# ole_fatchain.net
KiCad netlist of a schematic drawn in Altium Designer
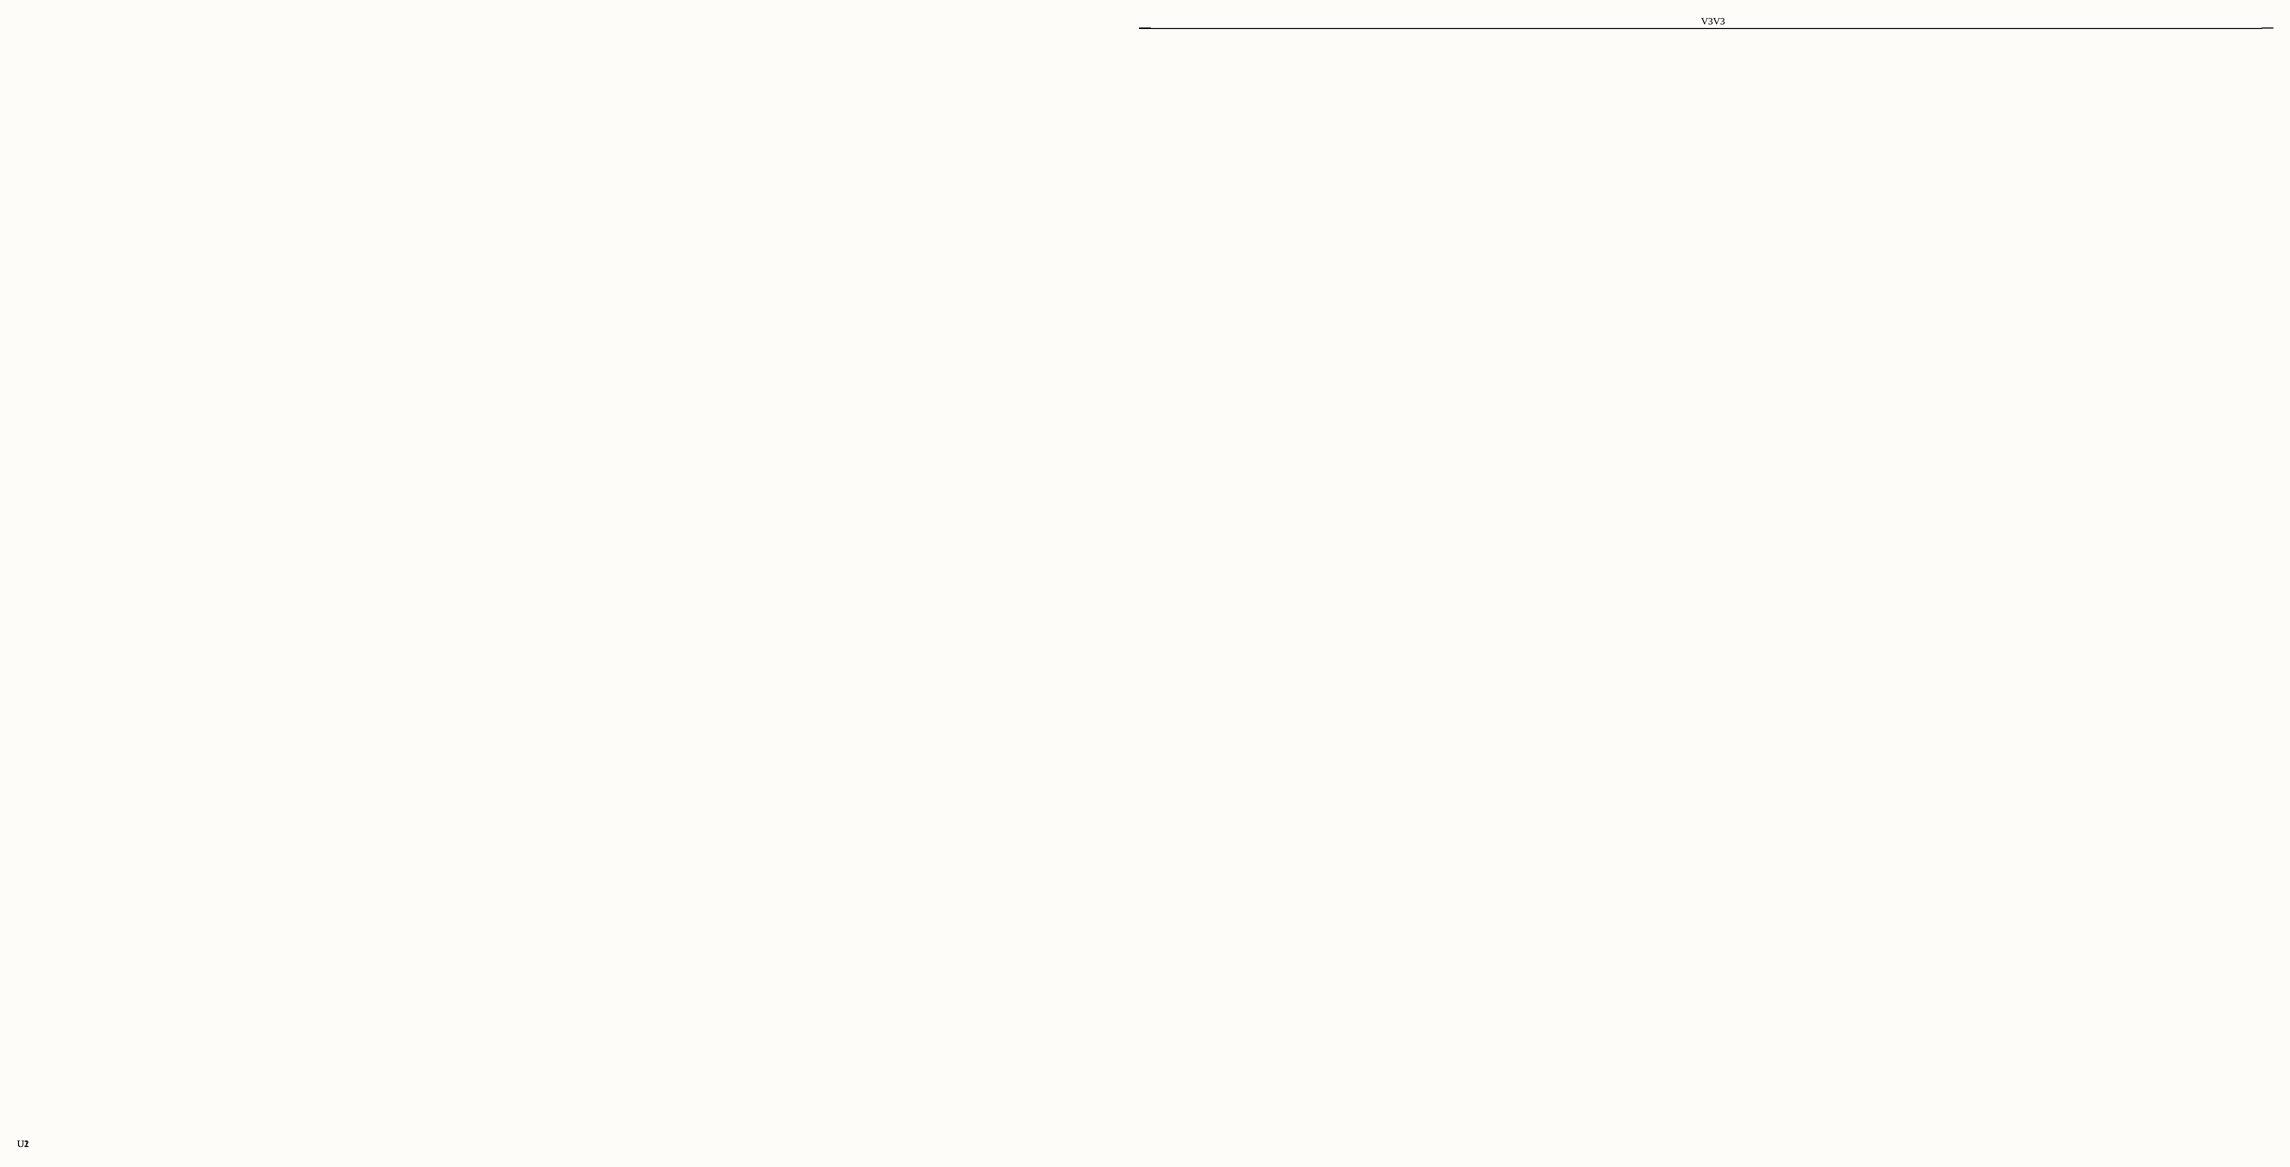
[diagram p0: ole_fatchain.SchDoc]

(export (version "E")
  (design (tool "Eeschema 10.0.6"))
  (components
    (comp (ref "U1") (value "~") (libsource (lib "altium-import") (part "root_0_RES_")))
    (comp (ref "U2") (value "~") (libsource (lib "altium-import") (part "root_0_CAP_")))
  )
  (nets
    (net (code "1") (name "/V3V3") (class "Default")
      (node (ref "U1") (pin "1") (pinfunction "P0.25_1") (pintype "passive"))
      (node (ref "U2") (pin "1") (pinfunction "VDD_1") (pintype "power_in"))
    )
  )
)
